# CONNECTEUR_4.net
KiCad netlist of a schematic drawn in Altium Designer
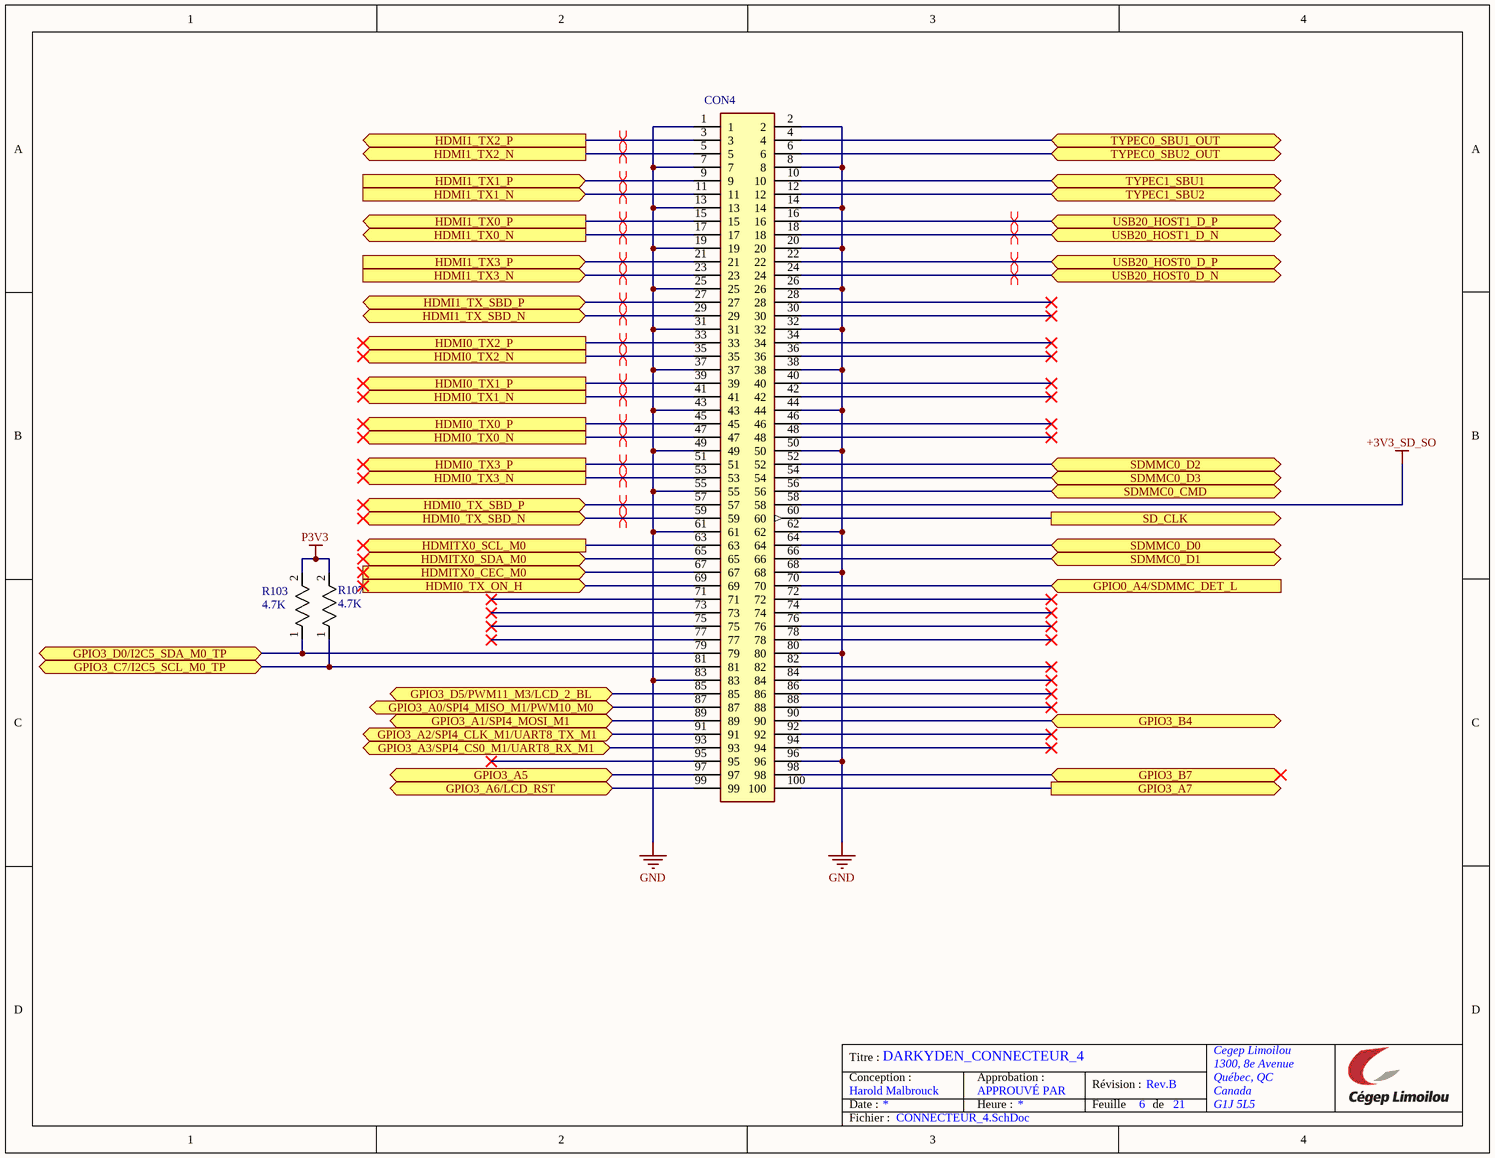
[diagram p0: CONNECTEUR_4.SchDoc]

(export (version "E")
  (design (tool "Eeschema 10.0.6"))
  (components
    (comp (ref "CON4")
      (value "DF40HC")
      (footprint "DF40HC30100DS04V51_MOD")
      (description "Stacking Board Connector, DF40 Series, Receptacle, 0.4 mm, 100, Surface Mount, G")
      (fields
        (field (name "MOUSER PART NUMBER") "798-DF40HC30100DS451")
        (field (name "ARROW PART NUMBER") "DF40HC(3.0)-100DS-0.4V(51")
      )
      (libsource (lib "DARKYDEN") (part "DF40HC(3.0)-100DS-0.4V(51)"))
    )
    (comp (ref "R103")
      (value "4.7K")
      (footprint "RESC1608X55N")
      (description "4.7K Ohm 0.1% 0.1W 0603 ±25ppm/°C Molded SMD Punched Carrier T/R")
      (fields
        (field (name "MANUFACTURER") "Panasonic")
        (field (name "MANUFACTURER PART NUMBER") "ERA-3AEB472V")
      )
      (libsource (lib "DARKYDEN") (part "ERA-3AEB472V"))
    )
    (comp (ref "R107")
      (value "4.7K")
      (footprint "RESC1608X55N")
      (description "4.7K Ohm 0.1% 0.1W 0603 ±25ppm/°C Molded SMD Punched Carrier T/R")
      (fields
        (field (name "MANUFACTURER") "Panasonic")
        (field (name "MANUFACTURER PART NUMBER") "ERA-3AEB472V")
      )
      (libsource (lib "DARKYDEN") (part "ERA-3AEB472V"))
    )
  )
  (nets
    (net (code "1") (name "+3V3_SD_SO") (class "Default")
      (node (ref "CON4") (pin "58") (pinfunction "58_58") (pintype "passive"))
    )
    (net (code "2") (name "/GPIO0_A4{slash}SDMMC_DET_L") (class "Default")
      (node (ref "CON4") (pin "70") (pinfunction "70_70") (pintype "passive"))
    )
    (net (code "3") (name "/GPIO3_A0{slash}SPI4_MISO_M1{slash}PWM10_M0") (class "Default")
      (node (ref "CON4") (pin "87") (pinfunction "87_87") (pintype "passive"))
    )
    (net (code "4") (name "/GPIO3_A1{slash}SPI4_MOSI_M1") (class "Default")
      (node (ref "CON4") (pin "89") (pinfunction "89_89") (pintype "passive"))
    )
    (net (code "5") (name "/GPIO3_A2{slash}SPI4_CLK_M1{slash}UART8_TX_M1") (class "Default")
      (node (ref "CON4") (pin "91") (pinfunction "91_91") (pintype "passive"))
    )
    (net (code "6") (name "/GPIO3_A3{slash}SPI4_CS0_M1{slash}UART8_RX_M1") (class "Default")
      (node (ref "CON4") (pin "93") (pinfunction "93_93") (pintype "passive"))
    )
    (net (code "7") (name "/GPIO3_A5") (class "Default")
      (node (ref "CON4") (pin "97") (pinfunction "97_97") (pintype "passive"))
    )
    (net (code "8") (name "/GPIO3_A6{slash}LCD_RST") (class "Default")
      (node (ref "CON4") (pin "99") (pinfunction "99_99") (pintype "passive"))
    )
    (net (code "9") (name "/GPIO3_A7") (class "Default")
      (node (ref "CON4") (pin "100") (pinfunction "100_100") (pintype "passive"))
    )
    (net (code "10") (name "/GPIO3_B4") (class "Default")
      (node (ref "CON4") (pin "90") (pinfunction "90_90") (pintype "passive"))
    )
    (net (code "11") (name "/GPIO3_B7") (class "Default")
      (node (ref "CON4") (pin "98") (pinfunction "98_98") (pintype "passive"))
    )
    (net (code "12") (name "/GPIO3_C7{slash}I2C5_SCL_M0_TP") (class "Default")
      (node (ref "CON4") (pin "81") (pinfunction "81_81") (pintype "passive"))
      (node (ref "R107") (pin "1") (pinfunction "1_1") (pintype "passive"))
    )
    (net (code "13") (name "/GPIO3_D0{slash}I2C5_SDA_M0_TP") (class "Default")
      (node (ref "CON4") (pin "79") (pinfunction "79_79") (pintype "passive"))
      (node (ref "R103") (pin "1") (pinfunction "1_1") (pintype "passive"))
    )
    (net (code "14") (name "/GPIO3_D5{slash}PWM11_M3{slash}LCD_2_BL") (class "Default")
      (node (ref "CON4") (pin "85") (pinfunction "85_85") (pintype "passive"))
    )
    (net (code "15") (name "/HDMI0_TX0_N") (class "Default")
      (node (ref "CON4") (pin "47") (pinfunction "47_47") (pintype "passive"))
    )
    (net (code "16") (name "/HDMI0_TX0_P") (class "Default")
      (node (ref "CON4") (pin "45") (pinfunction "45_45") (pintype "passive"))
    )
    (net (code "17") (name "/HDMI0_TX1_N") (class "Default")
      (node (ref "CON4") (pin "41") (pinfunction "41_41") (pintype "passive"))
    )
    (net (code "18") (name "/HDMI0_TX1_P") (class "Default")
      (node (ref "CON4") (pin "39") (pinfunction "39_39") (pintype "passive"))
    )
    (net (code "19") (name "/HDMI0_TX2_N") (class "Default")
      (node (ref "CON4") (pin "35") (pinfunction "35_35") (pintype "passive"))
    )
    (net (code "20") (name "/HDMI0_TX2_P") (class "Default")
      (node (ref "CON4") (pin "33") (pinfunction "33_33") (pintype "passive"))
    )
    (net (code "21") (name "/HDMI0_TX3_N") (class "Default")
      (node (ref "CON4") (pin "53") (pinfunction "53_53") (pintype "passive"))
    )
    (net (code "22") (name "/HDMI0_TX3_P") (class "Default")
      (node (ref "CON4") (pin "51") (pinfunction "51_51") (pintype "passive"))
    )
    (net (code "23") (name "/HDMI0_TX_ON_H") (class "Default")
      (node (ref "CON4") (pin "69") (pinfunction "69_69") (pintype "passive"))
    )
    (net (code "24") (name "/HDMI0_TX_SBD_N") (class "Default")
      (node (ref "CON4") (pin "59") (pinfunction "59_59") (pintype "passive"))
    )
    (net (code "25") (name "/HDMI0_TX_SBD_P") (class "Default")
      (node (ref "CON4") (pin "57") (pinfunction "57_57") (pintype "passive"))
    )
    (net (code "26") (name "/HDMI1_TX0_N") (class "Default")
      (node (ref "CON4") (pin "17") (pinfunction "17_17") (pintype "passive"))
    )
    (net (code "27") (name "/HDMI1_TX0_P") (class "Default")
      (node (ref "CON4") (pin "15") (pinfunction "15_15") (pintype "passive"))
    )
    (net (code "28") (name "/HDMI1_TX1_N") (class "Default")
      (node (ref "CON4") (pin "11") (pinfunction "11_11") (pintype "passive"))
    )
    (net (code "29") (name "/HDMI1_TX1_P") (class "Default")
      (node (ref "CON4") (pin "9") (pinfunction "9_9") (pintype "passive"))
    )
    (net (code "30") (name "/HDMI1_TX2_N") (class "Default")
      (node (ref "CON4") (pin "5") (pinfunction "5_5") (pintype "passive"))
    )
    (net (code "31") (name "/HDMI1_TX2_P") (class "Default")
      (node (ref "CON4") (pin "3") (pinfunction "3_3") (pintype "passive"))
    )
    (net (code "32") (name "/HDMI1_TX3_N") (class "Default")
      (node (ref "CON4") (pin "23") (pinfunction "23_23") (pintype "passive"))
    )
    (net (code "33") (name "/HDMI1_TX3_P") (class "Default")
      (node (ref "CON4") (pin "21") (pinfunction "21_21") (pintype "passive"))
    )
    (net (code "34") (name "/HDMI1_TX_SBD_N") (class "Default")
      (node (ref "CON4") (pin "29") (pinfunction "29_29") (pintype "passive"))
    )
    (net (code "35") (name "/HDMI1_TX_SBD_P") (class "Default")
      (node (ref "CON4") (pin "27") (pinfunction "27_27") (pintype "passive"))
    )
    (net (code "36") (name "/HDMITX0_CEC_M0") (class "Default")
      (node (ref "CON4") (pin "67") (pinfunction "67_67") (pintype "passive"))
    )
    (net (code "37") (name "/HDMITX0_SCL_M0") (class "Default")
      (node (ref "CON4") (pin "63") (pinfunction "63_63") (pintype "passive"))
    )
    (net (code "38") (name "/HDMITX0_SDA_M0") (class "Default")
      (node (ref "CON4") (pin "65") (pinfunction "65_65") (pintype "passive"))
    )
    (net (code "39") (name "/SDMMC0_CMD") (class "Default")
      (node (ref "CON4") (pin "56") (pinfunction "56_56") (pintype "passive"))
    )
    (net (code "40") (name "/SDMMC0_D0") (class "Default")
      (node (ref "CON4") (pin "64") (pinfunction "64_64") (pintype "passive"))
    )
    (net (code "41") (name "/SDMMC0_D1") (class "Default")
      (node (ref "CON4") (pin "66") (pinfunction "66_66") (pintype "passive"))
    )
    (net (code "42") (name "/SDMMC0_D2") (class "Default")
      (node (ref "CON4") (pin "52") (pinfunction "52_52") (pintype "passive"))
    )
    (net (code "43") (name "/SDMMC0_D3") (class "Default")
      (node (ref "CON4") (pin "54") (pinfunction "54_54") (pintype "passive"))
    )
    (net (code "44") (name "/SD_CLK") (class "Default")
      (node (ref "CON4") (pin "60") (pinfunction "60_60") (pintype "output"))
    )
    (net (code "45") (name "/TYPEC0_SBU1_OUT") (class "Default")
      (node (ref "CON4") (pin "4") (pinfunction "4_4") (pintype "passive"))
    )
    (net (code "46") (name "/TYPEC0_SBU2_OUT") (class "Default")
      (node (ref "CON4") (pin "6") (pinfunction "6_6") (pintype "passive"))
    )
    (net (code "47") (name "/TYPEC1_SBU1") (class "Default")
      (node (ref "CON4") (pin "10") (pinfunction "10_10") (pintype "passive"))
    )
    (net (code "48") (name "/TYPEC1_SBU2") (class "Default")
      (node (ref "CON4") (pin "12") (pinfunction "12_12") (pintype "passive"))
    )
    (net (code "49") (name "/USB20_HOST0_D_N") (class "Default")
      (node (ref "CON4") (pin "24") (pinfunction "24_24") (pintype "passive"))
    )
    (net (code "50") (name "/USB20_HOST0_D_P") (class "Default")
      (node (ref "CON4") (pin "22") (pinfunction "22_22") (pintype "passive"))
    )
    (net (code "51") (name "/USB20_HOST1_D_N") (class "Default")
      (node (ref "CON4") (pin "18") (pinfunction "18_18") (pintype "passive"))
    )
    (net (code "52") (name "/USB20_HOST1_D_P") (class "Default")
      (node (ref "CON4") (pin "16") (pinfunction "16_16") (pintype "passive"))
    )
    (net (code "53") (name "GND") (class "Default")
      (node (ref "CON4") (pin "1") (pinfunction "1_1") (pintype "passive"))
      (node (ref "CON4") (pin "13") (pinfunction "13_13") (pintype "passive"))
      (node (ref "CON4") (pin "14") (pinfunction "14_14") (pintype "passive"))
      (node (ref "CON4") (pin "19") (pinfunction "19_19") (pintype "passive"))
      (node (ref "CON4") (pin "2") (pinfunction "2_2") (pintype "passive"))
      (node (ref "CON4") (pin "20") (pinfunction "20_20") (pintype "passive"))
      (node (ref "CON4") (pin "25") (pinfunction "25_25") (pintype "passive"))
      (node (ref "CON4") (pin "26") (pinfunction "26_26") (pintype "passive"))
      (node (ref "CON4") (pin "31") (pinfunction "31_31") (pintype "passive"))
      (node (ref "CON4") (pin "32") (pinfunction "32_32") (pintype "passive"))
      (node (ref "CON4") (pin "37") (pinfunction "37_37") (pintype "passive"))
      (node (ref "CON4") (pin "38") (pinfunction "38_38") (pintype "passive"))
      (node (ref "CON4") (pin "43") (pinfunction "43_43") (pintype "passive"))
      (node (ref "CON4") (pin "44") (pinfunction "44_44") (pintype "passive"))
      (node (ref "CON4") (pin "49") (pinfunction "49_49") (pintype "passive"))
      (node (ref "CON4") (pin "50") (pinfunction "50_50") (pintype "passive"))
      (node (ref "CON4") (pin "55") (pinfunction "55_55") (pintype "passive"))
      (node (ref "CON4") (pin "61") (pinfunction "61_61") (pintype "passive"))
      (node (ref "CON4") (pin "62") (pinfunction "62_62") (pintype "passive"))
      (node (ref "CON4") (pin "68") (pinfunction "68_68") (pintype "passive"))
      (node (ref "CON4") (pin "7") (pinfunction "7_7") (pintype "passive"))
      (node (ref "CON4") (pin "8") (pinfunction "8_8") (pintype "passive"))
      (node (ref "CON4") (pin "80") (pinfunction "80_80") (pintype "passive"))
      (node (ref "CON4") (pin "83") (pinfunction "83_83") (pintype "passive"))
      (node (ref "CON4") (pin "96") (pinfunction "96_96") (pintype "passive"))
    )
    (net (code "54") (name "P3V3") (class "Default")
      (node (ref "R103") (pin "2") (pinfunction "2_2") (pintype "passive"))
      (node (ref "R107") (pin "2") (pinfunction "2_2") (pintype "passive"))
    )
    (net (code "55") (name "unconnected-(CON4-Pad28)") (class "Default")
      (node (ref "CON4") (pin "28") (pinfunction "28_28") (pintype "passive+no_connect"))
    )
    (net (code "56") (name "unconnected-(CON4-Pad30)") (class "Default")
      (node (ref "CON4") (pin "30") (pinfunction "30_30") (pintype "passive+no_connect"))
    )
    (net (code "57") (name "unconnected-(CON4-Pad34)") (class "Default")
      (node (ref "CON4") (pin "34") (pinfunction "34_34") (pintype "passive+no_connect"))
    )
    (net (code "58") (name "unconnected-(CON4-Pad36)") (class "Default")
      (node (ref "CON4") (pin "36") (pinfunction "36_36") (pintype "passive+no_connect"))
    )
    (net (code "59") (name "unconnected-(CON4-Pad40)") (class "Default")
      (node (ref "CON4") (pin "40") (pinfunction "40_40") (pintype "passive+no_connect"))
    )
    (net (code "60") (name "unconnected-(CON4-Pad42)") (class "Default")
      (node (ref "CON4") (pin "42") (pinfunction "42_42") (pintype "passive+no_connect"))
    )
    (net (code "61") (name "unconnected-(CON4-Pad46)") (class "Default")
      (node (ref "CON4") (pin "46") (pinfunction "46_46") (pintype "passive+no_connect"))
    )
    (net (code "62") (name "unconnected-(CON4-Pad48)") (class "Default")
      (node (ref "CON4") (pin "48") (pinfunction "48_48") (pintype "passive+no_connect"))
    )
    (net (code "63") (name "unconnected-(CON4-Pad71)") (class "Default")
      (node (ref "CON4") (pin "71") (pinfunction "71_71") (pintype "passive+no_connect"))
    )
    (net (code "64") (name "unconnected-(CON4-Pad72)") (class "Default")
      (node (ref "CON4") (pin "72") (pinfunction "72_72") (pintype "passive+no_connect"))
    )
    (net (code "65") (name "unconnected-(CON4-Pad73)") (class "Default")
      (node (ref "CON4") (pin "73") (pinfunction "73_73") (pintype "passive+no_connect"))
    )
    (net (code "66") (name "unconnected-(CON4-Pad74)") (class "Default")
      (node (ref "CON4") (pin "74") (pinfunction "74_74") (pintype "passive+no_connect"))
    )
    (net (code "67") (name "unconnected-(CON4-Pad75)") (class "Default")
      (node (ref "CON4") (pin "75") (pinfunction "75_75") (pintype "passive+no_connect"))
    )
    (net (code "68") (name "unconnected-(CON4-Pad76)") (class "Default")
      (node (ref "CON4") (pin "76") (pinfunction "76_76") (pintype "passive+no_connect"))
    )
    (net (code "69") (name "unconnected-(CON4-Pad77)") (class "Default")
      (node (ref "CON4") (pin "77") (pinfunction "77_77") (pintype "passive+no_connect"))
    )
    (net (code "70") (name "unconnected-(CON4-Pad78)") (class "Default")
      (node (ref "CON4") (pin "78") (pinfunction "78_78") (pintype "passive+no_connect"))
    )
    (net (code "71") (name "unconnected-(CON4-Pad82)") (class "Default")
      (node (ref "CON4") (pin "82") (pinfunction "82_82") (pintype "passive+no_connect"))
    )
    (net (code "72") (name "unconnected-(CON4-Pad84)") (class "Default")
      (node (ref "CON4") (pin "84") (pinfunction "84_84") (pintype "passive+no_connect"))
    )
    (net (code "73") (name "unconnected-(CON4-Pad86)") (class "Default")
      (node (ref "CON4") (pin "86") (pinfunction "86_86") (pintype "passive+no_connect"))
    )
    (net (code "74") (name "unconnected-(CON4-Pad88)") (class "Default")
      (node (ref "CON4") (pin "88") (pinfunction "88_88") (pintype "passive+no_connect"))
    )
    (net (code "75") (name "unconnected-(CON4-Pad92)") (class "Default")
      (node (ref "CON4") (pin "92") (pinfunction "92_92") (pintype "passive+no_connect"))
    )
    (net (code "76") (name "unconnected-(CON4-Pad94)") (class "Default")
      (node (ref "CON4") (pin "94") (pinfunction "94_94") (pintype "passive+no_connect"))
    )
    (net (code "77") (name "unconnected-(CON4-Pad95)") (class "Default")
      (node (ref "CON4") (pin "95") (pinfunction "95_95") (pintype "passive+no_connect"))
    )
  )
)
